# MCU.net
KiCad netlist of a schematic drawn in Altium Designer
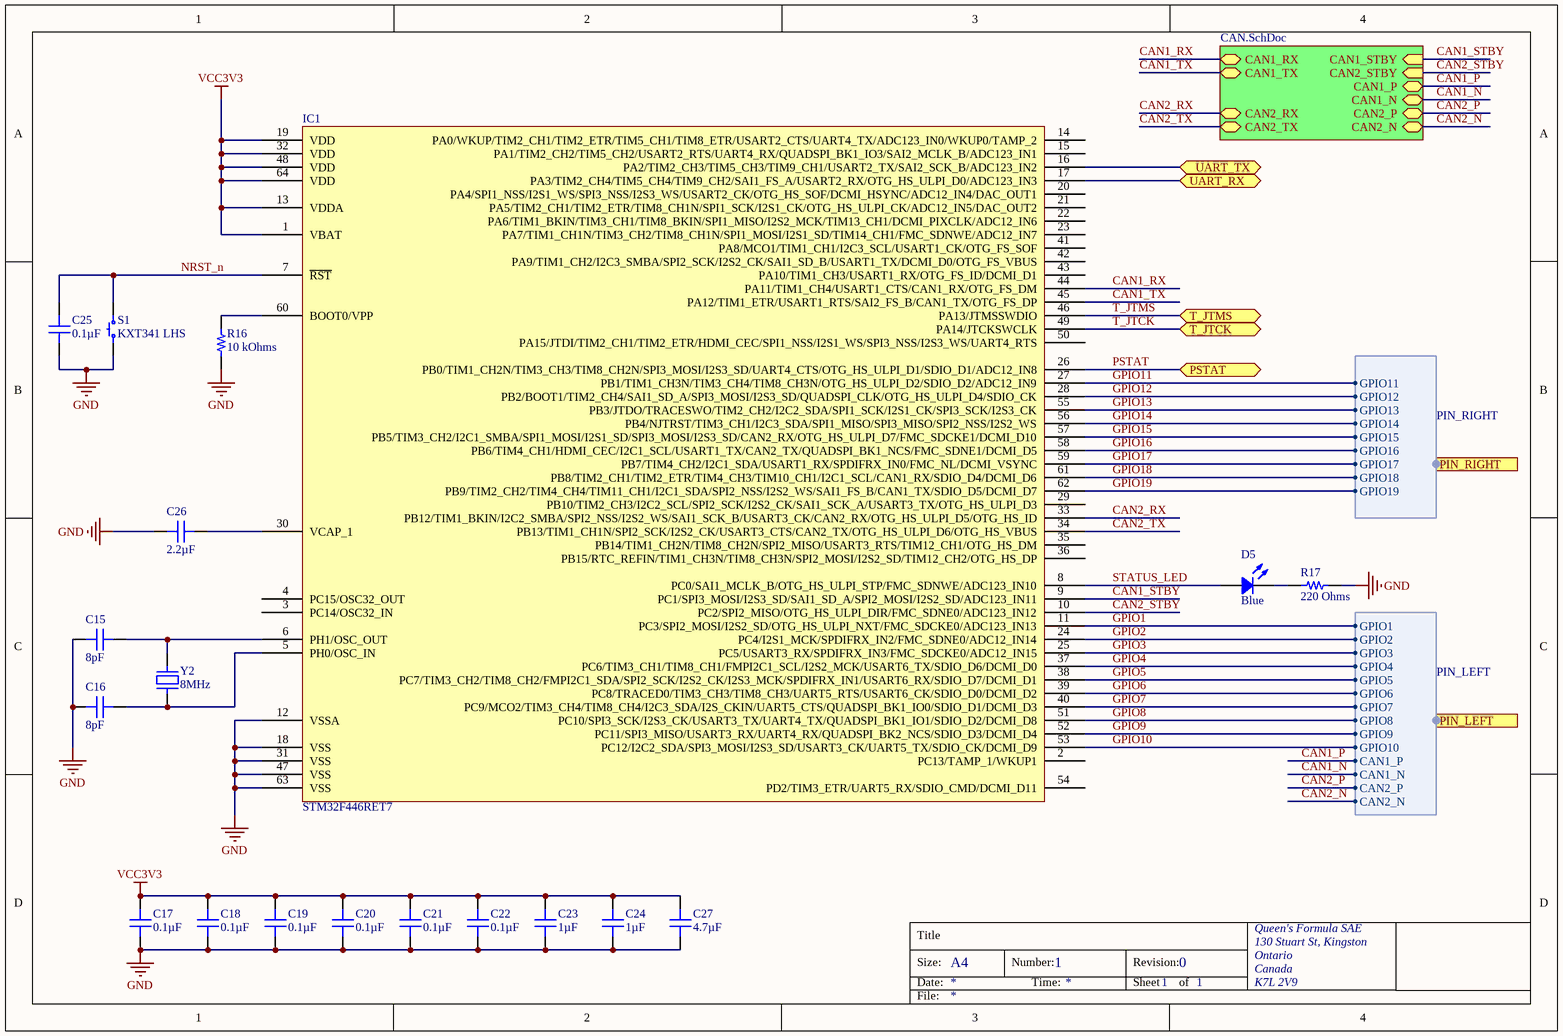
[diagram p0: MCU.SchDoc]

(export (version "E")
  (design (tool "Eeschema 10.0.6"))
  (components
    (comp (ref "C15")
      (value "8pF")
      (footprint "CAP 0402_1005")
      (description "CAP CER 8PF 50V NP0 0402")
      (fields
        (field (name "PART NUMBER") "C1005NP01H080D050BA")
        (field (name "MANUFACTURER") "TDK Corporation")
      )
      (libsource (lib "Celestial") (part "Capacitor"))
    )
    (comp (ref "C16")
      (value "8pF")
      (footprint "CAP 0402_1005")
      (description "CAP CER 8PF 50V NP0 0402")
      (fields
        (field (name "PART NUMBER") "C1005NP01H080D050BA")
        (field (name "MANUFACTURER") "TDK Corporation")
      )
      (libsource (lib "Celestial") (part "Capacitor"))
    )
    (comp (ref "C17")
      (value "0.1µF")
      (footprint "CAP 0201_0603")
      (description "CAP CER 0.1UF 16V X5R 0201")
      (fields (field (name "PART NUMBER") "EMK063BJ104KP-F") (field (name "MANUFACTURER") "Taiyo Yuden"))
      (libsource (lib "Celestial") (part "Capacitor"))
    )
    (comp (ref "C18")
      (value "0.1µF")
      (footprint "CAP 0201_0603")
      (description "CAP CER 0.1UF 16V X5R 0201")
      (fields (field (name "PART NUMBER") "EMK063BJ104KP-F") (field (name "MANUFACTURER") "Taiyo Yuden"))
      (libsource (lib "Celestial") (part "Capacitor"))
    )
    (comp (ref "C19")
      (value "0.1µF")
      (footprint "CAP 0201_0603")
      (description "CAP CER 0.1UF 16V X5R 0201")
      (fields (field (name "PART NUMBER") "EMK063BJ104KP-F") (field (name "MANUFACTURER") "Taiyo Yuden"))
      (libsource (lib "Celestial") (part "Capacitor"))
    )
    (comp (ref "C20")
      (value "0.1µF")
      (footprint "CAP 0201_0603")
      (description "CAP CER 0.1UF 16V X5R 0201")
      (fields (field (name "PART NUMBER") "EMK063BJ104KP-F") (field (name "MANUFACTURER") "Taiyo Yuden"))
      (libsource (lib "Celestial") (part "Capacitor"))
    )
    (comp (ref "C21")
      (value "0.1µF")
      (footprint "CAP 0201_0603")
      (description "CAP CER 0.1UF 16V X5R 0201")
      (fields (field (name "PART NUMBER") "EMK063BJ104KP-F") (field (name "MANUFACTURER") "Taiyo Yuden"))
      (libsource (lib "Celestial") (part "Capacitor"))
    )
    (comp (ref "C22")
      (value "0.1µF")
      (footprint "CAP 0201_0603")
      (description "CAP CER 0.1UF 16V X5R 0201")
      (fields (field (name "PART NUMBER") "EMK063BJ104KP-F") (field (name "MANUFACTURER") "Taiyo Yuden"))
      (libsource (lib "Celestial") (part "Capacitor"))
    )
    (comp (ref "C23")
      (value "1µF")
      (footprint "CAP 0201_0603")
      (description "CAP CER 1UF 10V X5R 0201")
      (fields
        (field (name "PART NUMBER") "GRM033R61A105ME15D")
        (field (name "MANUFACTURER") "Murata Electronics")
      )
      (libsource (lib "Celestial") (part "Capacitor"))
    )
    (comp (ref "C24")
      (value "1µF")
      (footprint "CAP 0201_0603")
      (description "CAP CER 1UF 10V X5R 0201")
      (fields
        (field (name "PART NUMBER") "GRM033R61A105ME15D")
        (field (name "MANUFACTURER") "Murata Electronics")
      )
      (libsource (lib "Celestial") (part "Capacitor"))
    )
    (comp (ref "C25")
      (value "0.1µF")
      (footprint "CAP 0201_0603")
      (description "CAP CER 0.1UF 16V X5R 0201")
      (fields (field (name "PART NUMBER") "EMK063BJ104KP-F") (field (name "MANUFACTURER") "Taiyo Yuden"))
      (libsource (lib "Celestial") (part "Capacitor"))
    )
    (comp (ref "C26")
      (value "2.2µF")
      (footprint "CAP 0201_0603")
      (description "CAP CER 2.2UF 10V X5R 0201")
      (fields
        (field (name "PART NUMBER") "GRM033R61A225ME47D")
        (field (name "MANUFACTURER") "Murata Electronics")
      )
      (libsource (lib "Celestial") (part "Capacitor"))
    )
    (comp (ref "C27")
      (value "4.7µF")
      (footprint "CAP 0201_0603")
      (description "CAP CER 4.7UF 6.3V X5R 0201")
      (fields
        (field (name "PART NUMBER") "GRM035R60J475ME15D")
        (field (name "MANUFACTURER") "Murata Electronics")
      )
      (libsource (lib "Celestial") (part "Capacitor"))
    )
    (comp (ref "D5")
      (value "Blue")
      (footprint "LED 0402_1005 BLUE")
      (description "LED BLUE CLEAR CHIP SMD")
      (fields (field (name "PART NUMBER") "APHHS1005QBC/D") (field (name "MANUFACTURER") "Kingbright"))
      (libsource (lib "Celestial") (part "LED"))
    )
    (comp (ref "IC1")
      (value "STM32F446RET7")
      (footprint "ST LQFP-64 10X10MM")
      (description "IC MCU 32BIT 512KB FLASH 64LQFP")
      (fields (field (name "MANUFACTURER") "STMicroelectronics"))
      (libsource (lib "Celestial") (part "ST STM32F446 64PIN"))
    )
    (comp (ref "R16")
      (value "10 kOhms")
      (footprint "RES 0201_0603")
      (description "RES SMD 10K OHM 1% 1/20W 0201")
      (fields (field (name "PART NUMBER") "CRCW020110K0FKED") (field (name "MANUFACTURER") "Vishay Dale"))
      (libsource (lib "Celestial") (part "Resistor"))
    )
    (comp (ref "R17")
      (value "220 Ohms")
      (footprint "RES 0201_0603")
      (description "RES 220 OHM 1% 1/20W 0201")
      (fields
        (field (name "PART NUMBER") "RK73H1HTTC2200F")
        (field (name "MANUFACTURER") "KOA Speer Electronics, Inc.")
      )
      (libsource (lib "Celestial") (part "Resistor"))
    )
    (comp (ref "S1")
      (value "KXT341 LHS")
      (footprint "C&K KXT3")
      (description "SWITCH TACTILE SPST-NO 0.02A 15V")
      (fields (field (name "MANUFACTURER") "C&K"))
      (libsource (lib "Celestial") (part "SPST-NO 2 PIN"))
    )
    (comp (ref "Y2")
      (value "8MHz")
      (footprint "NDK NX3225GD")
      (description "CRYSTAL 8.0000MHZ 8PF SMD")
      (fields
        (field (name "PART NUMBER") "NX3225GD-8MHZ-STD-CRA-3")
        (field (name "MANUFACTURER") "NDK America, Inc.")
      )
      (libsource (lib "Celestial") (part "NDK NX3225GD"))
    )
  )
  (nets
    (net (code "5") (name "/CAN1_RX") (class "Default")
      (node (ref "IC1") (pin "44") (pinfunction "PA11/TIM1_CH4/USART1_CTS/CAN1_RX/OTG_FS_DM_44") (pintype "passive"))
    )
    (net (code "6") (name "/CAN1_STBY") (class "Default")
      (node (ref "IC1") (pin "9") (pinfunction "PC1/SPI3_MOSI/I2S3_SD/SAI1_SD_A/SPI2_MOSI/I2S2_SD/ADC123_IN11_9") (pintype "passive"))
    )
    (net (code "7") (name "/CAN1_TX") (class "Default")
      (node (ref "IC1") (pin "45") (pinfunction "PA12/TIM1_ETR/USART1_RTS/SAI2_FS_B/CAN1_TX/OTG_FS_DP_45") (pintype "passive"))
    )
    (net (code "10") (name "/CAN2_RX") (class "Default")
      (node (ref "IC1") (pin "33") (pinfunction "PB12/TIM1_BKIN/I2C2_SMBA/SPI2_NSS/I2S2_WS/SAI1_SCK_B/USART3_CK/CAN2_RX/OTG_HS_ULPI_D5/OTG_HS_ID_33") (pintype "passive"))
    )
    (net (code "11") (name "/CAN2_STBY") (class "Default")
      (node (ref "IC1") (pin "10") (pinfunction "PC2/SPI2_MISO/OTG_HS_ULPI_DIR/FMC_SDNE0/ADC123_IN12_10") (pintype "passive"))
    )
    (net (code "12") (name "/CAN2_TX") (class "Default")
      (node (ref "IC1") (pin "34") (pinfunction "PB13/TIM1_CH1N/SPI2_SCK/I2S2_CK/USART3_CTS/CAN2_TX/OTG_HS_ULPI_D6/OTG_HS_VBUS_34") (pintype "passive"))
    )
    (net (code "13") (name "/GPIO1") (class "Default")
      (node (ref "IC1") (pin "11") (pinfunction "PC3/SPI2_MOSI/I2S2_SD/OTG_HS_ULPI_NXT/FMC_SDCKE0/ADC123_IN13_11") (pintype "passive"))
    )
    (net (code "14") (name "/GPIO2") (class "Default")
      (node (ref "IC1") (pin "24") (pinfunction "PC4/I2S1_MCK/SPDIFRX_IN2/FMC_SDNE0/ADC12_IN14_24") (pintype "passive"))
    )
    (net (code "15") (name "/GPIO3") (class "Default")
      (node (ref "IC1") (pin "25") (pinfunction "PC5/USART3_RX/SPDIFRX_IN3/FMC_SDCKE0/ADC12_IN15_25") (pintype "passive"))
    )
    (net (code "16") (name "/GPIO4") (class "Default")
      (node (ref "IC1") (pin "37") (pinfunction "PC6/TIM3_CH1/TIM8_CH1/FMPI2C1_SCL/I2S2_MCK/USART6_TX/SDIO_D6/DCMI_D0_37") (pintype "passive"))
    )
    (net (code "17") (name "/GPIO5") (class "Default")
      (node (ref "IC1") (pin "38") (pinfunction "PC7/TIM3_CH2/TIM8_CH2/FMPI2C1_SDA/SPI2_SCK/I2S2_CK/I2S3_MCK/SPDIFRX_IN1/USART6_RX/SDIO_D7/DCMI_D1_38") (pintype "passive"))
    )
    (net (code "18") (name "/GPIO6") (class "Default")
      (node (ref "IC1") (pin "39") (pinfunction "PC8/TRACED0/TIM3_CH3/TIM8_CH3/UART5_RTS/USART6_CK/SDIO_D0/DCMI_D2_39") (pintype "passive"))
    )
    (net (code "19") (name "/GPIO7") (class "Default")
      (node (ref "IC1") (pin "40") (pinfunction "PC9/MCO2/TIM3_CH4/TIM8_CH4/I2C3_SDA/I2S_CKIN/UART5_CTS/QUADSPI_BK1_IO0/SDIO_D1/DCMI_D3_40") (pintype "passive"))
    )
    (net (code "20") (name "/GPIO8") (class "Default")
      (node (ref "IC1") (pin "51") (pinfunction "PC10/SPI3_SCK/I2S3_CK/USART3_TX/UART4_TX/QUADSPI_BK1_IO1/SDIO_D2/DCMI_D8_51") (pintype "passive"))
    )
    (net (code "21") (name "/GPIO9") (class "Default")
      (node (ref "IC1") (pin "52") (pinfunction "PC11/SPI3_MISO/USART3_RX/UART4_RX/QUADSPI_BK2_NCS/SDIO_D3/DCMI_D4_52") (pintype "passive"))
    )
    (net (code "22") (name "/GPIO10") (class "Default")
      (node (ref "IC1") (pin "53") (pinfunction "PC12/I2C2_SDA/SPI3_MOSI/I2S3_SD/USART3_CK/UART5_TX/SDIO_CK/DCMI_D9_53") (pintype "passive"))
    )
    (net (code "23") (name "/GPIO11") (class "Default")
      (node (ref "IC1") (pin "27") (pinfunction "PB1/TIM1_CH3N/TIM3_CH4/TIM8_CH3N/OTG_HS_ULPI_D2/SDIO_D2/ADC12_IN9_27") (pintype "passive"))
    )
    (net (code "24") (name "/GPIO12") (class "Default")
      (node (ref "IC1") (pin "28") (pinfunction "PB2/BOOT1/TIM2_CH4/SAI1_SD_A/SPI3_MOSI/I2S3_SD/QUADSPI_CLK/OTG_HS_ULPI_D4/SDIO_CK_28") (pintype "passive"))
    )
    (net (code "25") (name "/GPIO13") (class "Default")
      (node (ref "IC1") (pin "55") (pinfunction "PB3/JTDO/TRACESWO/TIM2_CH2/I2C2_SDA/SPI1_SCK/I2S1_CK/SPI3_SCK/I2S3_CK_55") (pintype "passive"))
    )
    (net (code "26") (name "/GPIO14") (class "Default")
      (node (ref "IC1") (pin "56") (pinfunction "PB4/NJTRST/TIM3_CH1/I2C3_SDA/SPI1_MISO/SPI3_MISO/SPI2_NSS/I2S2_WS_56") (pintype "passive"))
    )
    (net (code "27") (name "/GPIO15") (class "Default")
      (node (ref "IC1") (pin "57") (pinfunction "PB5/TIM3_CH2/I2C1_SMBA/SPI1_MOSI/I2S1_SD/SPI3_MOSI/I2S3_SD/CAN2_RX/OTG_HS_ULPI_D7/FMC_SDCKE1/DCMI_D10_57") (pintype "passive"))
    )
    (net (code "28") (name "/GPIO16") (class "Default")
      (node (ref "IC1") (pin "58") (pinfunction "PB6/TIM4_CH1/HDMI_CEC/I2C1_SCL/USART1_TX/CAN2_TX/QUADSPI_BK1_NCS/FMC_SDNE1/DCMI_D5_58") (pintype "passive"))
    )
    (net (code "29") (name "/GPIO17") (class "Default")
      (node (ref "IC1") (pin "59") (pinfunction "PB7/TIM4_CH2/I2C1_SDA/USART1_RX/SPDIFRX_IN0/FMC_NL/DCMI_VSYNC_59") (pintype "passive"))
    )
    (net (code "30") (name "/GPIO18") (class "Default")
      (node (ref "IC1") (pin "61") (pinfunction "PB8/TIM2_CH1/TIM2_ETR/TIM4_CH3/TIM10_CH1/I2C1_SCL/CAN1_RX/SDIO_D4/DCMI_D6_61") (pintype "passive"))
    )
    (net (code "31") (name "/GPIO19") (class "Default")
      (node (ref "IC1") (pin "62") (pinfunction "PB9/TIM2_CH2/TIM4_CH4/TIM11_CH1/I2C1_SDA/SPI2_NSS/I2S2_WS/SAI1_FS_B/CAN1_TX/SDIO_D5/DCMI_D7_62") (pintype "passive"))
    )
    (net (code "32") (name "/NRST_n") (class "Default")
      (node (ref "C25") (pin "2") (pinfunction "2_2") (pintype "passive"))
      (node (ref "IC1") (pin "7") (pinfunction "~{RST}_7") (pintype "passive"))
      (node (ref "S1") (pin "2") (pinfunction "2_2") (pintype "passive"))
    )
    (net (code "33") (name "/PSTAT") (class "Default")
      (node (ref "IC1") (pin "26") (pinfunction "PB0/TIM1_CH2N/TIM3_CH3/TIM8_CH2N/SPI3_MOSI/I2S3_SD/UART4_CTS/OTG_HS_ULPI_D1/SDIO_D1/ADC12_IN8_26") (pintype "passive"))
    )
    (net (code "34") (name "/STATUS_LED") (class "Default")
      (node (ref "D5") (pin "1") (pinfunction "1_1") (pintype "passive"))
      (node (ref "IC1") (pin "8") (pinfunction "PC0/SAI1_MCLK_B/OTG_HS_ULPI_STP/FMC_SDNWE/ADC123_IN10_8") (pintype "passive"))
    )
    (net (code "35") (name "/T_JTCK") (class "Default")
      (node (ref "IC1") (pin "49") (pinfunction "PA14/JTCKSWCLK_49") (pintype "passive"))
    )
    (net (code "36") (name "/T_JTMS") (class "Default")
      (node (ref "IC1") (pin "46") (pinfunction "PA13/JTMSSWDIO_46") (pintype "passive"))
    )
    (net (code "37") (name "/UART_RX") (class "Default")
      (node (ref "IC1") (pin "17") (pinfunction "PA3/TIM2_CH4/TIM5_CH4/TIM9_CH2/SAI1_FS_A/USART2_RX/OTG_HS_ULPI_D0/ADC123_IN3_17") (pintype "passive"))
    )
    (net (code "38") (name "/UART_TX") (class "Default")
      (node (ref "IC1") (pin "16") (pinfunction "PA2/TIM2_CH3/TIM5_CH3/TIM9_CH1/USART2_TX/SAI2_SCK_B/ADC123_IN2_16") (pintype "passive"))
    )
    (net (code "41") (name "GND") (class "Default")
      (node (ref "C15") (pin "1") (pinfunction "1_1") (pintype "passive"))
      (node (ref "C16") (pin "1") (pinfunction "1_1") (pintype "passive"))
      (node (ref "C17") (pin "1") (pinfunction "1_1") (pintype "passive"))
      (node (ref "C18") (pin "1") (pinfunction "1_1") (pintype "passive"))
      (node (ref "C19") (pin "1") (pinfunction "1_1") (pintype "passive"))
      (node (ref "C20") (pin "1") (pinfunction "1_1") (pintype "passive"))
      (node (ref "C21") (pin "1") (pinfunction "1_1") (pintype "passive"))
      (node (ref "C22") (pin "1") (pinfunction "1_1") (pintype "passive"))
      (node (ref "C23") (pin "1") (pinfunction "1_1") (pintype "passive"))
      (node (ref "C24") (pin "1") (pinfunction "1_1") (pintype "passive"))
      (node (ref "C25") (pin "1") (pinfunction "1_1") (pintype "passive"))
      (node (ref "C26") (pin "2") (pinfunction "2_2") (pintype "passive"))
      (node (ref "C27") (pin "1") (pinfunction "1_1") (pintype "passive"))
      (node (ref "IC1") (pin "12") (pinfunction "VSSA_12") (pintype "passive"))
      (node (ref "IC1") (pin "18") (pinfunction "VSS_18") (pintype "passive"))
      (node (ref "IC1") (pin "31") (pinfunction "VSS_31") (pintype "passive"))
      (node (ref "IC1") (pin "47") (pinfunction "VSS_47") (pintype "passive"))
      (node (ref "IC1") (pin "63") (pinfunction "VSS_63") (pintype "passive"))
      (node (ref "R16") (pin "1") (pinfunction "1_1") (pintype "passive"))
      (node (ref "R17") (pin "2") (pinfunction "2_2") (pintype "passive"))
      (node (ref "S1") (pin "1") (pinfunction "1_1") (pintype "passive"))
    )
    (net (code "42") (name "Net-(D5-Pad2)") (class "Default")
      (node (ref "D5") (pin "2") (pinfunction "2_2") (pintype "passive"))
      (node (ref "R17") (pin "1") (pinfunction "1_1") (pintype "passive"))
    )
    (net (code "43") (name "Net-(IC1-BOOT0{slash}VPP)") (class "Default")
      (node (ref "IC1") (pin "60") (pinfunction "BOOT0/VPP_60") (pintype "passive"))
      (node (ref "R16") (pin "2") (pinfunction "2_2") (pintype "passive"))
    )
    (net (code "44") (name "Net-(IC1-PH0{slash}OSC_IN)") (class "Default")
      (node (ref "C16") (pin "2") (pinfunction "2_2") (pintype "passive"))
      (node (ref "IC1") (pin "5") (pinfunction "PH0/OSC_IN_5") (pintype "passive"))
      (node (ref "Y2") (pin "1") (pinfunction "1_1") (pintype "passive"))
    )
    (net (code "45") (name "Net-(IC1-PH1{slash}OSC_OUT)") (class "Default")
      (node (ref "C15") (pin "2") (pinfunction "2_2") (pintype "passive"))
      (node (ref "IC1") (pin "6") (pinfunction "PH1/OSC_OUT_6") (pintype "passive"))
      (node (ref "Y2") (pin "2") (pinfunction "2_2") (pintype "passive"))
    )
    (net (code "46") (name "Net-(IC1-VCAP_1)") (class "Default")
      (node (ref "C26") (pin "1") (pinfunction "1_1") (pintype "passive"))
      (node (ref "IC1") (pin "30") (pinfunction "VCAP_1_30") (pintype "passive"))
    )
    (net (code "47") (name "VCC3V3") (class "Default")
      (node (ref "C17") (pin "2") (pinfunction "2_2") (pintype "passive"))
      (node (ref "C18") (pin "2") (pinfunction "2_2") (pintype "passive"))
      (node (ref "C19") (pin "2") (pinfunction "2_2") (pintype "passive"))
      (node (ref "C20") (pin "2") (pinfunction "2_2") (pintype "passive"))
      (node (ref "C21") (pin "2") (pinfunction "2_2") (pintype "passive"))
      (node (ref "C22") (pin "2") (pinfunction "2_2") (pintype "passive"))
      (node (ref "C23") (pin "2") (pinfunction "2_2") (pintype "passive"))
      (node (ref "C24") (pin "2") (pinfunction "2_2") (pintype "passive"))
      (node (ref "C27") (pin "2") (pinfunction "2_2") (pintype "passive"))
      (node (ref "IC1") (pin "1") (pinfunction "VBAT_1") (pintype "passive"))
      (node (ref "IC1") (pin "13") (pinfunction "VDDA_13") (pintype "passive"))
      (node (ref "IC1") (pin "19") (pinfunction "VDD_19") (pintype "passive"))
      (node (ref "IC1") (pin "32") (pinfunction "VDD_32") (pintype "passive"))
      (node (ref "IC1") (pin "48") (pinfunction "VDD_48") (pintype "passive"))
      (node (ref "IC1") (pin "64") (pinfunction "VDD_64") (pintype "passive"))
    )
    (net (code "48") (name "unconnected-(IC1-PA0{slash}WKUP{slash}TIM2_CH1{slash}TIM2_ETR{slash}TIM5_CH1{slash}TIM8_ETR{slash}USART2_CTS{slash}UART4_TX{slash}ADC123_IN0{slash}WKUP0{slash}TAMP_2-Pad14)") (class "Default")
      (node (ref "IC1") (pin "14") (pinfunction "PA0/WKUP/TIM2_CH1/TIM2_ETR/TIM5_CH1/TIM8_ETR/USART2_CTS/UART4_TX/ADC123_IN0/WKUP0/TAMP_2_14") (pintype "passive"))
    )
    (net (code "49") (name "unconnected-(IC1-PA1{slash}TIM2_CH2{slash}TIM5_CH2{slash}USART2_RTS{slash}UART4_RX{slash}QUADSPI_BK1_IO3{slash}SAI2_MCLK_B{slash}ADC123_IN1-Pad15)") (class "Default")
      (node (ref "IC1") (pin "15") (pinfunction "PA1/TIM2_CH2/TIM5_CH2/USART2_RTS/UART4_RX/QUADSPI_BK1_IO3/SAI2_MCLK_B/ADC123_IN1_15") (pintype "passive"))
    )
    (net (code "50") (name "unconnected-(IC1-PA4{slash}SPI1_NSS{slash}I2S1_WS{slash}SPI3_NSS{slash}I2S3_WS{slash}USART2_CK{slash}OTG_HS_SOF{slash}DCMI_HSYNC{slash}ADC12_IN4{slash}DAC_OUT1-Pad20)") (class "Default")
      (node (ref "IC1") (pin "20") (pinfunction "PA4/SPI1_NSS/I2S1_WS/SPI3_NSS/I2S3_WS/USART2_CK/OTG_HS_SOF/DCMI_HSYNC/ADC12_IN4/DAC_OUT1_20") (pintype "passive"))
    )
    (net (code "51") (name "unconnected-(IC1-PA5{slash}TIM2_CH1{slash}TIM2_ETR{slash}TIM8_CH1N{slash}SPI1_SCK{slash}I2S1_CK{slash}OTG_HS_ULPI_CK{slash}ADC12_IN5{slash}DAC_OUT2-Pad21)") (class "Default")
      (node (ref "IC1") (pin "21") (pinfunction "PA5/TIM2_CH1/TIM2_ETR/TIM8_CH1N/SPI1_SCK/I2S1_CK/OTG_HS_ULPI_CK/ADC12_IN5/DAC_OUT2_21") (pintype "passive"))
    )
    (net (code "52") (name "unconnected-(IC1-PA6{slash}TIM1_BKIN{slash}TIM3_CH1{slash}TIM8_BKIN{slash}SPI1_MISO{slash}I2S2_MCK{slash}TIM13_CH1{slash}DCMI_PIXCLK{slash}ADC12_IN6-Pad22)") (class "Default")
      (node (ref "IC1") (pin "22") (pinfunction "PA6/TIM1_BKIN/TIM3_CH1/TIM8_BKIN/SPI1_MISO/I2S2_MCK/TIM13_CH1/DCMI_PIXCLK/ADC12_IN6_22") (pintype "passive"))
    )
    (net (code "53") (name "unconnected-(IC1-PA7{slash}TIM1_CH1N{slash}TIM3_CH2{slash}TIM8_CH1N{slash}SPI1_MOSI{slash}I2S1_SD{slash}TIM14_CH1{slash}FMC_SDNWE{slash}ADC12_IN7-Pad23)") (class "Default")
      (node (ref "IC1") (pin "23") (pinfunction "PA7/TIM1_CH1N/TIM3_CH2/TIM8_CH1N/SPI1_MOSI/I2S1_SD/TIM14_CH1/FMC_SDNWE/ADC12_IN7_23") (pintype "passive"))
    )
    (net (code "54") (name "unconnected-(IC1-PA8{slash}MCO1{slash}TIM1_CH1{slash}I2C3_SCL{slash}USART1_CK{slash}OTG_FS_SOF-Pad41)") (class "Default")
      (node (ref "IC1") (pin "41") (pinfunction "PA8/MCO1/TIM1_CH1/I2C3_SCL/USART1_CK/OTG_FS_SOF_41") (pintype "passive"))
    )
    (net (code "55") (name "unconnected-(IC1-PA9{slash}TIM1_CH2{slash}I2C3_SMBA{slash}SPI2_SCK{slash}I2S2_CK{slash}SAI1_SD_B{slash}USART1_TX{slash}DCMI_D0{slash}OTG_FS_VBUS-Pad42)") (class "Default")
      (node (ref "IC1") (pin "42") (pinfunction "PA9/TIM1_CH2/I2C3_SMBA/SPI2_SCK/I2S2_CK/SAI1_SD_B/USART1_TX/DCMI_D0/OTG_FS_VBUS_42") (pintype "passive"))
    )
    (net (code "56") (name "unconnected-(IC1-PA10{slash}TIM1_CH3{slash}USART1_RX{slash}OTG_FS_ID{slash}DCMI_D1-Pad43)") (class "Default")
      (node (ref "IC1") (pin "43") (pinfunction "PA10/TIM1_CH3/USART1_RX/OTG_FS_ID/DCMI_D1_43") (pintype "passive"))
    )
    (net (code "57") (name "unconnected-(IC1-PA15{slash}JTDI{slash}TIM2_CH1{slash}TIM2_ETR{slash}HDMI_CEC{slash}SPI1_NSS{slash}I2S1_WS{slash}SPI3_NSS{slash}I2S3_WS{slash}UART4_RTS-Pad50)") (class "Default")
      (node (ref "IC1") (pin "50") (pinfunction "PA15/JTDI/TIM2_CH1/TIM2_ETR/HDMI_CEC/SPI1_NSS/I2S1_WS/SPI3_NSS/I2S3_WS/UART4_RTS_50") (pintype "passive"))
    )
    (net (code "58") (name "unconnected-(IC1-PB10{slash}TIM2_CH3{slash}I2C2_SCL{slash}SPI2_SCK{slash}I2S2_CK{slash}SAI1_SCK_A{slash}USART3_TX{slash}OTG_HS_ULPI_D3-Pad29)") (class "Default")
      (node (ref "IC1") (pin "29") (pinfunction "PB10/TIM2_CH3/I2C2_SCL/SPI2_SCK/I2S2_CK/SAI1_SCK_A/USART3_TX/OTG_HS_ULPI_D3_29") (pintype "passive"))
    )
    (net (code "59") (name "unconnected-(IC1-PB14{slash}TIM1_CH2N{slash}TIM8_CH2N{slash}SPI2_MISO{slash}USART3_RTS{slash}TIM12_CH1{slash}OTG_HS_DM-Pad35)") (class "Default")
      (node (ref "IC1") (pin "35") (pinfunction "PB14/TIM1_CH2N/TIM8_CH2N/SPI2_MISO/USART3_RTS/TIM12_CH1/OTG_HS_DM_35") (pintype "passive"))
    )
    (net (code "60") (name "unconnected-(IC1-PB15{slash}RTC_REFIN{slash}TIM1_CH3N{slash}TIM8_CH3N{slash}SPI2_MOSI{slash}I2S2_SD{slash}TIM12_CH2{slash}OTG_HS_DP-Pad36)") (class "Default")
      (node (ref "IC1") (pin "36") (pinfunction "PB15/RTC_REFIN/TIM1_CH3N/TIM8_CH3N/SPI2_MOSI/I2S2_SD/TIM12_CH2/OTG_HS_DP_36") (pintype "passive"))
    )
    (net (code "61") (name "unconnected-(IC1-PC13{slash}TAMP_1{slash}WKUP1-Pad2)") (class "Default")
      (node (ref "IC1") (pin "2") (pinfunction "PC13/TAMP_1/WKUP1_2") (pintype "passive"))
    )
    (net (code "62") (name "unconnected-(IC1-PC14{slash}OSC32_IN-Pad3)") (class "Default")
      (node (ref "IC1") (pin "3") (pinfunction "PC14/OSC32_IN_3") (pintype "passive"))
    )
    (net (code "63") (name "unconnected-(IC1-PC15{slash}OSC32_OUT-Pad4)") (class "Default")
      (node (ref "IC1") (pin "4") (pinfunction "PC15/OSC32_OUT_4") (pintype "passive"))
    )
    (net (code "64") (name "unconnected-(IC1-PD2{slash}TIM3_ETR{slash}UART5_RX{slash}SDIO_CMD{slash}DCMI_D11-Pad54)") (class "Default")
      (node (ref "IC1") (pin "54") (pinfunction "PD2/TIM3_ETR/UART5_RX/SDIO_CMD/DCMI_D11_54") (pintype "passive"))
    )
  )
)
